# Power_Input.net
KiCad netlist of a schematic drawn in Altium Designer
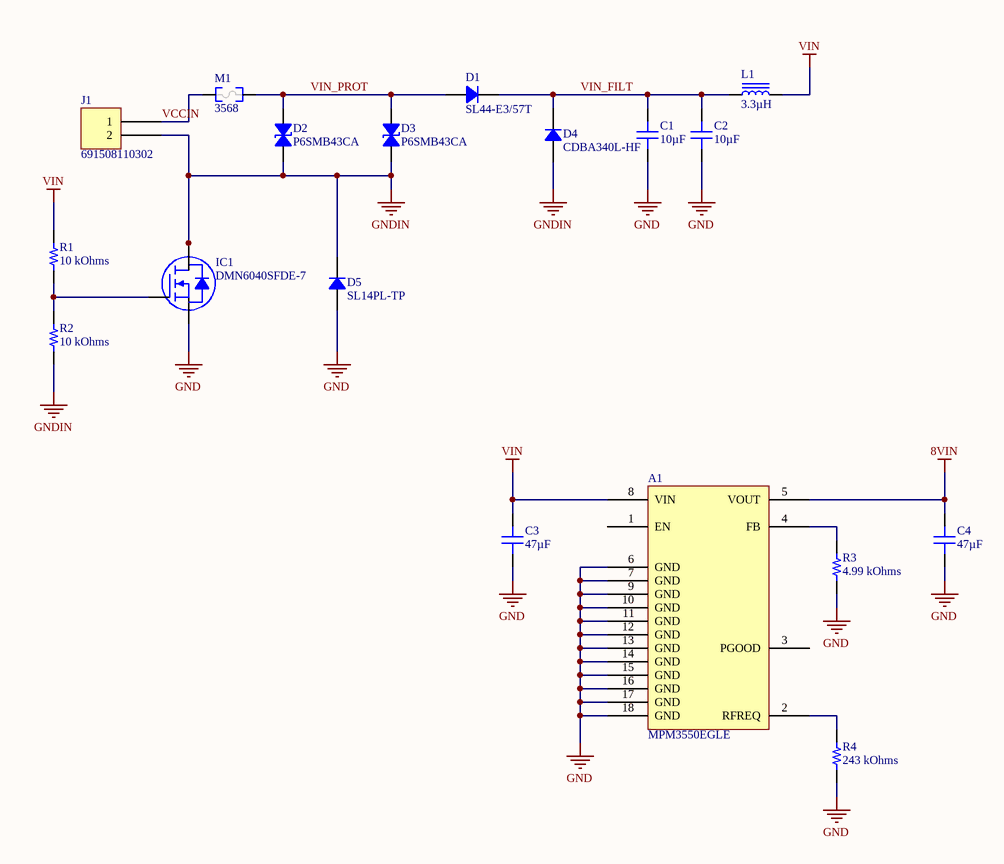
[diagram p0: Power Input.SchDoc]

(export (version "E")
  (design (tool "Eeschema 10.0.6"))
  (components
    (comp (ref "A1")
      (value "MPM3550EGLE")
      (footprint "MPS LGA-18 12x12x4.2mm")
      (description "DC/DC POWER MODULE 5A 1.0 TO 12.")
      (fields (field (name "MANUFACTURER") "Monolithic Power Systems Inc."))
      (libsource (lib "Celestial Altium Library - altium_library") (part "MPS MPM3550E"))
    )
    (comp (ref "C1")
      (value "10µF")
      (footprint "CAP 1210_3225 - 2.8MM")
      (description "CAP CER 10UF 50V X7R 1210")
      (fields
        (field (name "PART NUMBER") "CL32B106KBJNNNE")
        (field (name "MANUFACTURER") "Samsung Electro-Mechanics")
      )
      (libsource (lib "Celestial Altium Library - altium_library") (part "Capacitor"))
    )
    (comp (ref "C2")
      (value "10µF")
      (footprint "CAP 1210_3225 - 2.8MM")
      (description "CAP CER 10UF 50V X7R 1210")
      (fields
        (field (name "PART NUMBER") "CL32B106KBJNNNE")
        (field (name "MANUFACTURER") "Samsung Electro-Mechanics")
      )
      (libsource (lib "Celestial Altium Library - altium_library") (part "Capacitor"))
    )
    (comp (ref "C3")
      (value "47µF")
      (footprint "CAP 1210_3225 - 2.8MM")
      (description "CAP CER 47UF 10V X7R 1210")
      (fields (field (name "PART NUMBER") "LMK325B7476MM-PR") (field (name "MANUFACTURER") "Taiyo Yuden"))
      (libsource (lib "Celestial Altium Library - altium_library") (part "Capacitor"))
    )
    (comp (ref "C4")
      (value "47µF")
      (footprint "CAP 1210_3225 - 2.8MM")
      (description "CAP CER 47UF 10V X7R 1210")
      (fields (field (name "PART NUMBER") "LMK325B7476MM-PR") (field (name "MANUFACTURER") "Taiyo Yuden"))
      (libsource (lib "Celestial Altium Library - altium_library") (part "Capacitor"))
    )
    (comp (ref "D1")
      (value "SL44-E3/57T")
      (footprint "DO214AB SMC")
      (description "DIODE SCHOTTKY 40V 4A DO214AB")
      (fields (field (name "MANUFACTURER") "Vishay Semiconductor Diodes Division"))
      (libsource (lib "Celestial Altium Library - altium_library") (part "Diode"))
    )
    (comp (ref "D2")
      (value "P6SMB43CA")
      (footprint "DO214AA SMB")
      (description "TVS DIODE 36.8V 59.3V DO214AA")
      (fields (field (name "MANUFACTURER") "Bourns Inc."))
      (libsource (lib "Celestial Altium Library - altium_library") (part "Diode TVS"))
    )
    (comp (ref "D3")
      (value "P6SMB43CA")
      (footprint "DO214AA SMB")
      (description "TVS DIODE 36.8V 59.3V DO214AA")
      (fields (field (name "MANUFACTURER") "Bourns Inc."))
      (libsource (lib "Celestial Altium Library - altium_library") (part "Diode TVS"))
    )
    (comp (ref "D4")
      (value "CDBA340L-HF")
      (footprint "DO214AC SMA")
      (description "DIODE SCHOTTKY 40V 3A DO214AC")
      (fields (field (name "MANUFACTURER") "Comchip Technology"))
      (libsource (lib "Celestial Altium Library - altium_library") (part "Diode"))
    )
    (comp (ref "D5")
      (value "SL14PL-TP")
      (footprint "SOD123F")
      (description "DIODE SCHOTTKY 1A 40V SOD-123FL")
      (fields (field (name "MANUFACTURER") "Micro Commercial Co"))
      (libsource (lib "Celestial Altium Library - altium_library") (part "Diode"))
    )
    (comp (ref "IC1")
      (value "DMN6040SFDE-7")
      (footprint "DIODES U-DFN2020-6E")
      (description "MOSFET N-CH 60V 5.3A U-DFN")
      (fields (field (name "MANUFACTURER") "Diodes Incorporated"))
      (libsource (lib "Celestial Altium Library - altium_library") (part "DIODES INC MOSFET U-DFN2020-6 TYPE E"))
    )
    (comp (ref "J1")
      (value "691508110302")
      (footprint "WURTH 691508110302")
      (description "TERM BLOCK 2POS 3.5MM SMD")
      (fields (field (name "MANUFACTURER") "Würth Elektronik") (field (name "VOLTAGE") "300V"))
      (libsource (lib "Celestial Altium Library - altium_library") (part "2 Pin"))
    )
    (comp (ref "L1")
      (value "3.3µH")
      (footprint "BOURNS SRP5030T")
      (description "FIXED IND 3.3UH 5A 38 MOHM SMD")
      (fields (field (name "PART NUMBER") "SRP5030T-3R3M") (field (name "MANUFACTURER") "Bourns Inc."))
      (libsource (lib "Celestial Altium Library - altium_library") (part "Inductor"))
    )
    (comp (ref "M1")
      (value "3568")
      (footprint "KEYSTONE 3568")
      (description "FUSE HOLDER BLADE 500V 30A PCB")
      (fields (field (name "MANUFACTURER") "Keystone Electronics") (field (name "VOLTAGE") "500V"))
      (libsource (lib "Celestial Altium Library - altium_library") (part "FUSE HOLDER"))
    )
    (comp (ref "R1")
      (value "10 kOhms")
      (footprint "RES 0201_0603")
      (description "RES SMD 10K OHM 1% 1/20W 0201")
      (fields
        (field (name "PART NUMBER") "ERJ-1GNF1002C")
        (field (name "MANUFACTURER") "Panasonic Electronic Components")
      )
      (libsource (lib "Celestial Altium Library - altium_library") (part "Resistor"))
    )
    (comp (ref "R2")
      (value "10 kOhms")
      (footprint "RES 0201_0603")
      (description "RES SMD 10K OHM 1% 1/20W 0201")
      (fields
        (field (name "PART NUMBER") "ERJ-1GNF1002C")
        (field (name "MANUFACTURER") "Panasonic Electronic Components")
      )
      (libsource (lib "Celestial Altium Library - altium_library") (part "Resistor"))
    )
    (comp (ref "R3")
      (value "4.99 kOhms")
      (footprint "RES 0201_0603")
      (description "RES SMD 4.99K OHM 1% 1/20W 0201")
      (fields
        (field (name "PART NUMBER") "ERJ-1GNF4991C")
        (field (name "MANUFACTURER") "Panasonic Electronic Components")
      )
      (libsource (lib "Celestial Altium Library - altium_library") (part "Resistor"))
    )
    (comp (ref "R4")
      (value "243 kOhms")
      (footprint "RES 0201_0603")
      (description "RES SMD 243K OHM 1% 1/20W 0201")
      (fields
        (field (name "PART NUMBER") "ERJ-1GNF2433C")
        (field (name "MANUFACTURER") "Panasonic Electronic Components")
      )
      (libsource (lib "Celestial Altium Library - altium_library") (part "Resistor"))
    )
  )
  (nets
    (net (code "1") (name "/VCCIN") (class "Default")
      (node (ref "J1") (pin "1") (pinfunction "1_1") (pintype "passive"))
      (node (ref "M1") (pin "1") (pinfunction "1_1") (pintype "passive"))
    )
    (net (code "2") (name "/VIN_FILT") (class "Default")
      (node (ref "C1") (pin "2") (pinfunction "2_2") (pintype "passive"))
      (node (ref "C2") (pin "2") (pinfunction "2_2") (pintype "passive"))
      (node (ref "D1") (pin "2") (pinfunction "2_2") (pintype "passive"))
      (node (ref "D4") (pin "2") (pinfunction "2_2") (pintype "passive"))
      (node (ref "L1") (pin "1") (pinfunction "1_1") (pintype "passive"))
    )
    (net (code "3") (name "/VIN_PROT") (class "Default")
      (node (ref "D1") (pin "1") (pinfunction "1_1") (pintype "passive"))
      (node (ref "D2") (pin "2") (pinfunction "2_2") (pintype "passive"))
      (node (ref "D3") (pin "2") (pinfunction "2_2") (pintype "passive"))
      (node (ref "M1") (pin "2") (pinfunction "2_2") (pintype "passive"))
    )
    (net (code "4") (name "8VIN") (class "Default")
      (node (ref "A1") (pin "5") (pinfunction "VOUT_5") (pintype "passive"))
      (node (ref "C4") (pin "2") (pinfunction "2_2") (pintype "passive"))
    )
    (net (code "5") (name "GND") (class "Default")
      (node (ref "A1") (pin "10") (pinfunction "GND_10") (pintype "passive"))
      (node (ref "A1") (pin "11") (pinfunction "GND_11") (pintype "passive"))
      (node (ref "A1") (pin "12") (pinfunction "GND_12") (pintype "passive"))
      (node (ref "A1") (pin "13") (pinfunction "GND_13") (pintype "passive"))
      (node (ref "A1") (pin "14") (pinfunction "GND_14") (pintype "passive"))
      (node (ref "A1") (pin "15") (pinfunction "GND_15") (pintype "passive"))
      (node (ref "A1") (pin "16") (pinfunction "GND_16") (pintype "passive"))
      (node (ref "A1") (pin "17") (pinfunction "GND_17") (pintype "passive"))
      (node (ref "A1") (pin "18") (pinfunction "GND_18") (pintype "passive"))
      (node (ref "A1") (pin "6") (pinfunction "GND_6") (pintype "passive"))
      (node (ref "A1") (pin "7") (pinfunction "GND_7") (pintype "passive"))
      (node (ref "A1") (pin "9") (pinfunction "GND_9") (pintype "passive"))
      (node (ref "C1") (pin "1") (pinfunction "1_1") (pintype "passive"))
      (node (ref "C2") (pin "1") (pinfunction "1_1") (pintype "passive"))
      (node (ref "C3") (pin "1") (pinfunction "1_1") (pintype "passive"))
      (node (ref "C4") (pin "1") (pinfunction "1_1") (pintype "passive"))
      (node (ref "D5") (pin "1") (pinfunction "1_1") (pintype "passive"))
      (node (ref "IC1") (pin "S") (pinfunction "S_S") (pintype "passive"))
      (node (ref "R3") (pin "1") (pinfunction "1_1") (pintype "passive"))
      (node (ref "R4") (pin "1") (pinfunction "1_1") (pintype "passive"))
    )
    (net (code "6") (name "GNDIN") (class "Default")
      (node (ref "D2") (pin "1") (pinfunction "1_1") (pintype "passive"))
      (node (ref "D3") (pin "1") (pinfunction "1_1") (pintype "passive"))
      (node (ref "D4") (pin "1") (pinfunction "1_1") (pintype "passive"))
      (node (ref "D5") (pin "2") (pinfunction "2_2") (pintype "passive"))
      (node (ref "IC1") (pin "D") (pinfunction "Drain_D") (pintype "passive"))
      (node (ref "J1") (pin "2") (pinfunction "2_2") (pintype "passive"))
      (node (ref "R2") (pin "1") (pinfunction "1_1") (pintype "passive"))
    )
    (net (code "7") (name "Net-(A1-FB)") (class "Default")
      (node (ref "A1") (pin "4") (pinfunction "FB_4") (pintype "passive"))
      (node (ref "R3") (pin "2") (pinfunction "2_2") (pintype "passive"))
    )
    (net (code "8") (name "Net-(A1-RFREQ)") (class "Default")
      (node (ref "A1") (pin "2") (pinfunction "RFREQ_2") (pintype "passive"))
      (node (ref "R4") (pin "2") (pinfunction "2_2") (pintype "passive"))
    )
    (net (code "9") (name "Net-(IC1-PadG)") (class "Default")
      (node (ref "IC1") (pin "G") (pinfunction "G_G") (pintype "passive"))
      (node (ref "R1") (pin "2") (pinfunction "2_2") (pintype "passive"))
      (node (ref "R2") (pin "2") (pinfunction "2_2") (pintype "passive"))
    )
    (net (code "10") (name "VIN") (class "Default")
      (node (ref "A1") (pin "8") (pinfunction "VIN_8") (pintype "passive"))
      (node (ref "C3") (pin "2") (pinfunction "2_2") (pintype "passive"))
      (node (ref "L1") (pin "2") (pinfunction "2_2") (pintype "passive"))
      (node (ref "R1") (pin "1") (pinfunction "1_1") (pintype "passive"))
    )
    (net (code "11") (name "unconnected-(A1-EN-Pad1)") (class "Default")
      (node (ref "A1") (pin "1") (pinfunction "EN_1") (pintype "passive"))
    )
    (net (code "12") (name "unconnected-(A1-PGOOD-Pad3)") (class "Default")
      (node (ref "A1") (pin "3") (pinfunction "PGOOD_3") (pintype "passive"))
    )
  )
)
